# Switch.net
KiCad netlist of a schematic drawn in EAGLE
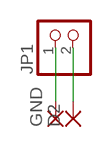
[diagram p0: schematic, sheet 1]

(export (version "E")
  (design (tool "Eeschema 10.0.6"))
  (components
    (comp (ref "D2")
      (value "2,15/1,0")
      (footprint "eagle-import:2,15_1,0")
      (libsource (lib "eagle-import") (part "2,15/1,0"))
    )
    (comp (ref "GND")
      (value "2,15/1,0")
      (footprint "eagle-import:2,15_1,0")
      (libsource (lib "eagle-import") (part "2,15/1,0"))
    )
    (comp (ref "JP1")
      (value "PINHD-1X2")
      (footprint "eagle-import:1X02")
      (libsource (lib "eagle-import") (part "PINHD-1X2"))
    )
  )
  (nets
    (net (code "1") (name "Net-(D2-P)") (class "Default")
      (node (ref "D2") (pin "1") (pinfunction "P_1") (pintype "passive"))
      (node (ref "JP1") (pin "2") (pinfunction "2_2") (pintype "passive"))
    )
    (net (code "2") (name "Net-(GND-P)") (class "Default")
      (node (ref "GND") (pin "1") (pinfunction "P_1") (pintype "passive"))
      (node (ref "JP1") (pin "1") (pinfunction "1_1") (pintype "passive"))
    )
  )
)
